# SCH15.net
KiCad netlist of a schematic drawn in Altium Designer
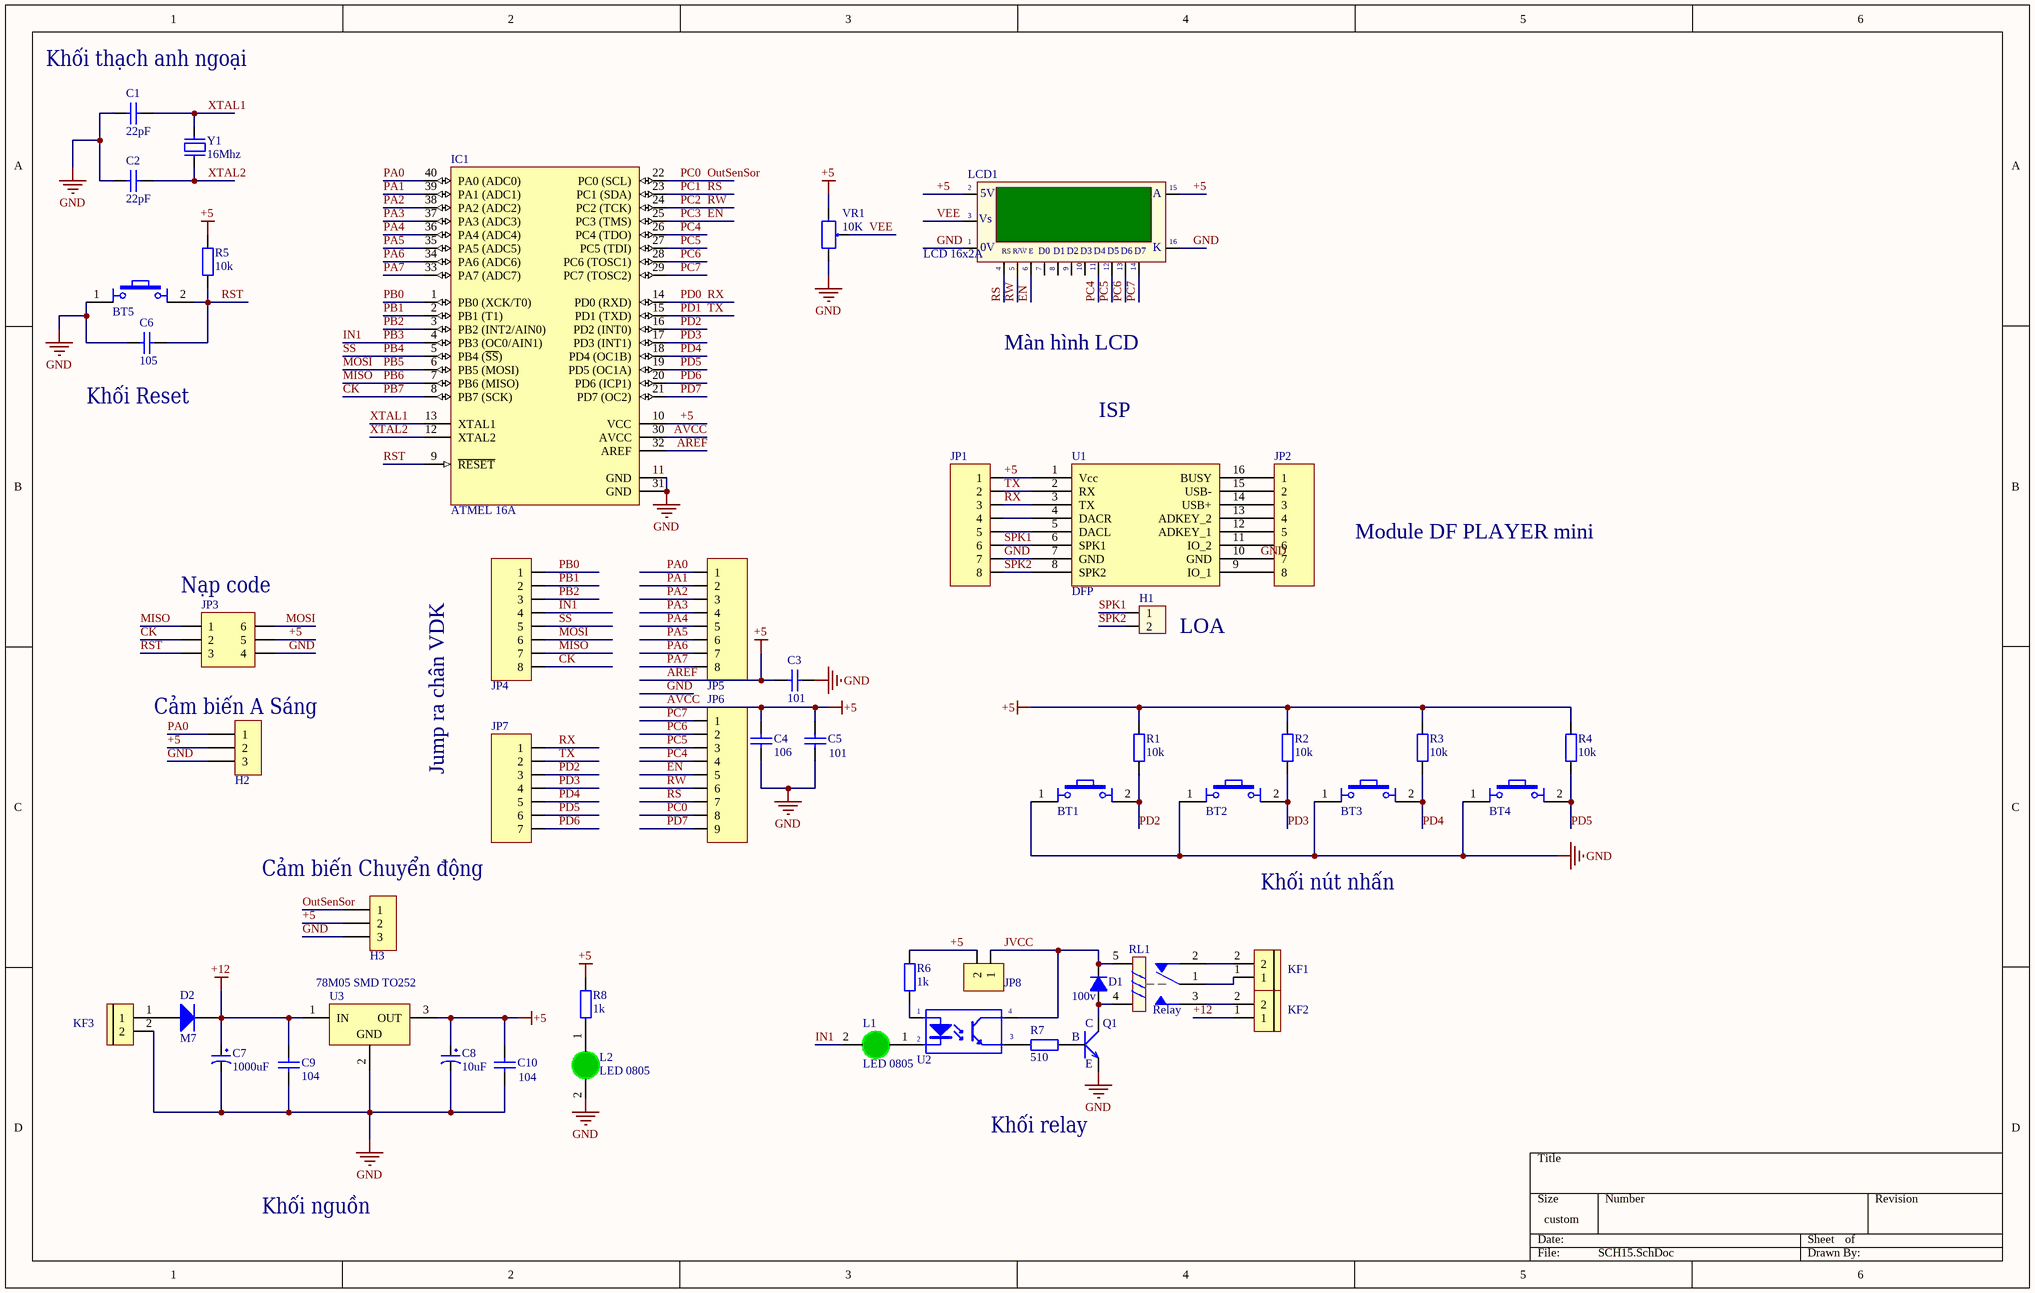
[diagram p0: SCH15.SchDoc]

(export (version "E")
  (design (tool "Eeschema 10.0.6"))
  (components
    (comp (ref "BT1")
      (value "Nut Nhan 4 Chan Cam 6x6")
      (footprint "Nut Nhan 4 Chan Cam 6x6")
      (description "Nut Nhan 4 Chan 6x6mm")
      (libsource (lib "Component") (part "Nut Nhan 4 Chan Cam 6x6"))
    )
    (comp (ref "BT2")
      (value "Nut Nhan 4 Chan Cam 6x6")
      (footprint "Nut Nhan 4 Chan Cam 6x6")
      (description "Nut Nhan 4 Chan 6x6mm")
      (libsource (lib "Component") (part "Nut Nhan 4 Chan Cam 6x6"))
    )
    (comp (ref "BT3")
      (value "Nut Nhan 4 Chan Cam 6x6")
      (footprint "Nut Nhan 4 Chan Cam 6x6")
      (description "Nut Nhan 4 Chan 6x6mm")
      (libsource (lib "Component") (part "Nut Nhan 4 Chan Cam 6x6"))
    )
    (comp (ref "BT4")
      (value "Nut Nhan 4 Chan Cam 6x6")
      (footprint "Nut Nhan 4 Chan Cam 6x6")
      (description "Nut Nhan 4 Chan 6x6mm")
      (libsource (lib "Component") (part "Nut Nhan 4 Chan Cam 6x6"))
    )
    (comp (ref "BT5")
      (value "Nut Nhan 4 Chan Cam 6x6")
      (footprint "Nut Nhan 4 Chan Cam 6x6")
      (description "Nut Nhan 4 Chan 6x6mm")
      (libsource (lib "Component") (part "Nut Nhan 4 Chan Cam 6x6"))
    )
    (comp (ref "C1")
      (value "22pF")
      (footprint "tu 0805")
      (description "Dán")
      (libsource (lib "Tu dien") (part "Tu 0805 22pF 50V 10%"))
    )
    (comp (ref "C2")
      (value "22pF")
      (footprint "tu 0805")
      (description "Dán")
      (libsource (lib "Tu dien") (part "Tu 0805 22pF 50V 10%"))
    )
    (comp (ref "C3")
      (value "101")
      (footprint "tu 0805")
      (description "Dán")
      (libsource (lib "Tu dien") (part "Tu 0805 101 50V 20%"))
    )
    (comp (ref "C4")
      (value "106")
      (footprint "tu 0805")
      (description "Dán")
      (libsource (lib "Tu dien") (part "Tu 0805 106 16V 10%"))
    )
    (comp (ref "C5")
      (value "101")
      (footprint "tu 0805")
      (description "Dán")
      (libsource (lib "Tu dien") (part "Tu 0805 101 50V 20%"))
    )
    (comp (ref "C6")
      (value "105")
      (footprint "tu 0805")
      (description "Dán")
      (libsource (lib "Tu dien") (part "Tu 0805 105 50V 10%"))
    )
    (comp (ref "C7")
      (value "1000uF")
      (footprint "tu hoa 8mm")
      (description "Cắm")
      (libsource (lib "Tu dien") (part "Tu Hoa 1000uF 16V 8x20"))
    )
    (comp (ref "C8")
      (value "10uF")
      (footprint "tu hoa 4mm")
      (description "Cắm")
      (libsource (lib "Tu dien") (part "Tu Hoa 10uF 16V 4x7"))
    )
    (comp (ref "C9")
      (value "104")
      (footprint "tu 0805")
      (description "Dán")
      (libsource (lib "Tu dien") (part "Tu 0805 104 50V 10%"))
    )
    (comp (ref "C10")
      (value "104")
      (footprint "tu 0805")
      (description "Dán")
      (libsource (lib "Tu dien") (part "Tu 0805 104 50V 10%"))
    )
    (comp (ref "D1")
      (value "100v")
      (footprint "DIODE ZENNER SMD SOD80")
      (description "Cắm")
      (libsource (lib "Diode") (part "Diode 1N4148"))
    )
    (comp (ref "D2")
      (value "M7")
      (footprint "DIODE SMA")
      (description "Dán")
      (libsource (lib "Diode") (part "Diode M7 ( 4007 )"))
    )
    (comp (ref "H1")
      (value "Header 2P 2.54 Duc Thang")
      (footprint "XH2.54M-2")
      (description "Cắm")
      (libsource (lib "Header") (part "Header 2P 2.54 Duc Thang"))
    )
    (comp (ref "H2")
      (value "Header 3P 2.54 Duc Thang")
      (footprint "XH2.54M-3")
      (description "Cắm")
      (libsource (lib "Header") (part "Header 3P 2.54 Duc Thang"))
    )
    (comp (ref "H3")
      (value "Header 3P 2.54 Duc Thang")
      (footprint "XH2.54M-3")
      (description "Cắm")
      (libsource (lib "Header") (part "Header 3P 2.54 Duc Thang"))
    )
    (comp (ref "IC1")
      (value "ATMEL 16A")
      (footprint "DIP40/W0.6")
      (description "8-Bit AVR Microcontroller with 16K Bytes of In-System Programmable Flash Memory")
      (libsource (lib "Thu Vien Chuan") (part "ATmega16A-PU"))
    )
    (comp (ref "JP1")
      (value "JP 1x8 2.54")
      (footprint "JP 1x8 DT")
      (description "Cắm")
      (libsource (lib "Jump") (part "JP 1x8 2.54 Duc Thang"))
    )
    (comp (ref "JP2")
      (value "JP 1x8 2.54")
      (footprint "JP 1x8 DT")
      (description "Cắm")
      (libsource (lib "") (part "JP 1x8 2.54 Duc Thang_1"))
    )
    (comp (ref "JP3")
      (value "JP 2x3 2.54")
      (footprint "JP 2x3 DT")
      (description "Cắm")
      (libsource (lib "Jump") (part "JP 2x3 2.54 Duc Thang"))
    )
    (comp (ref "JP4")
      (value "JP 1x8 2.54")
      (footprint "JP 1x8 DT")
      (description "Cắm")
      (libsource (lib "Jump") (part "JP 1x8 2.54 Duc Thang"))
    )
    (comp (ref "JP5")
      (value "JP 1x8 2.54")
      (footprint "JP 1x8 DT")
      (description "Cắm")
      (libsource (lib "") (part "JP 1x8 2.54 Duc Thang_1"))
    )
    (comp (ref "JP6")
      (value "JP 1x9 2.54")
      (footprint "JP 1x9 DT")
      (description "Cắm")
      (libsource (lib "Jump") (part "JP 1x9 2.54 Duc Thang"))
    )
    (comp (ref "JP7")
      (value "JP 1x7 2.54")
      (footprint "JP 1x7 DT")
      (description "Cắm")
      (libsource (lib "Jump") (part "JP 1x7 2.54 Duc Thang"))
    )
    (comp (ref "JP8")
      (value "JP 1x2 2.54")
      (footprint "JP 1x2 DT")
      (description "Cắm")
      (libsource (lib "Jump") (part "JP 1x2 2.54 Duc Thang"))
    )
    (comp (ref "KF1")
      (value "CON 2 KF301")
      (footprint "Con 2 KF301 5.08")
      (description "Cắm")
      (libsource (lib "") (part "CON 2 KF301_1"))
    )
    (comp (ref "KF2")
      (value "CON 2 KF301")
      (footprint "Con 2 KF301 5.08")
      (description "Cắm")
      (libsource (lib "") (part "CON 2 KF301_1"))
    )
    (comp (ref "KF3")
      (value "CON 2 KF301")
      (footprint "Con 2 KF301 5.08")
      (description "Cắm")
      (libsource (lib "Connector") (part "CON 2 KF301"))
    )
    (comp (ref "L1")
      (value "LED 0805")
      (footprint "LED-0805-Green")
      (description "Dán")
      (libsource (lib "Led") (part "LED 0805 Xanh La"))
    )
    (comp (ref "L2")
      (value "LED 0805")
      (footprint "LED-0805-Green")
      (description "Dán")
      (libsource (lib "Led") (part "LED 0805 Xanh La"))
    )
    (comp (ref "LCD1")
      (value "LCD 16x2A")
      (footprint "LCD16X2N")
      (description "LCD dipslay 16 char, 2 line")
      (libsource (lib "Thu Vien Chuan") (part "LCD16x2A"))
    )
    (comp (ref "Q1")
      (value "SMD-TRANSISTORS-NPN-25V-500MW(SOT-23)")
      (footprint "SOT 23-3")
      (description "Bipolar (BJT) Transistor NPN 25 V 500 mA 150MHz 300 mW Surface Mount SOT-23")
      (fields (field (name "MF") "UMW") (field (name "MP") "S8050"))
      (libsource (lib "05.IC") (part "SMD-TRANSISTORS-NPN-25V-500MW(SOT-23)"))
    )
    (comp (ref "R1")
      (value "10k")
      (footprint "tro smd 0805")
      (description "Dán")
      (libsource (lib "Dien Tro") (part "Tro 0805 1% 10k"))
    )
    (comp (ref "R2")
      (value "10k")
      (footprint "tro smd 0805")
      (description "Dán")
      (libsource (lib "Dien Tro") (part "Tro 0805 1% 10k"))
    )
    (comp (ref "R3")
      (value "10k")
      (footprint "tro smd 0805")
      (description "Dán")
      (libsource (lib "Dien Tro") (part "Tro 0805 1% 10k"))
    )
    (comp (ref "R4")
      (value "10k")
      (footprint "tro smd 0805")
      (description "Dán")
      (libsource (lib "Dien Tro") (part "Tro 0805 1% 10k"))
    )
    (comp (ref "R5")
      (value "10k")
      (footprint "tro smd 0805")
      (description "Dán")
      (libsource (lib "Dien Tro") (part "Tro 0805 1% 10k"))
    )
    (comp (ref "R6")
      (value "1k")
      (footprint "tro smd 0805")
      (description "Dán")
      (libsource (lib "Dien Tro") (part "Tro 0805 1% 1k"))
    )
    (comp (ref "R7")
      (value "510")
      (footprint "tro smd 0805")
      (description "Dán")
      (libsource (lib "Dien Tro") (part "Tro 0805 1% 1k"))
    )
    (comp (ref "R8")
      (value "1k")
      (footprint "tro smd 0805")
      (description "Dán")
      (libsource (lib "Dien Tro") (part "Tro 0805 1% 1k"))
    )
    (comp (ref "RL1")
      (value "Relay")
      (footprint "Relay 5 Chan SRD")
      (description "Relay 5 Chan")
      (libsource (lib "Component") (part "Relay 5 Chan SRD"))
    )
    (comp (ref "U1")
      (value "DFP")
      (footprint "DFPlayer")
      (description "DFPlayer")
      (libsource (lib "Module1") (part "DFPlayer"))
    )
    (comp (ref "U2")
      (value "OPTO PC817 DIP4")
      (footprint "DIP4")
      (description "Single Opto")
      (libsource (lib "IC") (part "OPTO PC817 DIP4"))
    )
    (comp (ref "U3")
      (value "78M05 SMD TO252")
      (footprint "TO252")
      (description "Dán")
      (libsource (lib "IC") (part "78M05 SMD TO252"))
    )
    (comp (ref "VR1")
      (value "10K")
      (footprint "Bien Tro Vi Chinh Dung")
      (description "Cắm")
      (libsource (lib "Dien Tro") (part "Bien Tro Tinh Chinh 1K Dung"))
    )
    (comp (ref "Y1")
      (value "16Mhz")
      (footprint "Thach Anh 2 chan cam")
      (description "Crystal For all Crystal 2pin.")
      (libsource (lib "Component") (part "Thach Anh 2 chan Cam"))
    )
  )
  (nets
    (net (code "1") (name "+5") (class "Default")
      (node (ref "C10") (pin "1") (pinfunction "1_1") (pintype "passive"))
      (node (ref "C3") (pin "1") (pinfunction "1_1") (pintype "passive"))
      (node (ref "C4") (pin "2") (pinfunction "2_2") (pintype "passive"))
      (node (ref "C5") (pin "1") (pinfunction "1_1") (pintype "passive"))
      (node (ref "C8") (pin "1") (pinfunction "1_1") (pintype "passive"))
      (node (ref "H2") (pin "2") (pinfunction "2_2") (pintype "passive"))
      (node (ref "H3") (pin "2") (pinfunction "2_2") (pintype "passive"))
      (node (ref "IC1") (pin "10") (pinfunction "VCC_10") (pintype "power_in"))
      (node (ref "IC1") (pin "30") (pinfunction "AVCC_30") (pintype "power_in"))
      (node (ref "IC1") (pin "32") (pinfunction "AREF_32") (pintype "power_in"))
      (node (ref "JP1") (pin "1") (pinfunction "1_1") (pintype "passive"))
      (node (ref "JP3") (pin "5") (pinfunction "5_5") (pintype "passive"))
      (node (ref "JP8") (pin "2") (pinfunction "2_2") (pintype "passive"))
      (node (ref "LCD1") (pin "15") (pinfunction "A_15") (pintype "passive"))
      (node (ref "LCD1") (pin "2") (pinfunction "VDD_2") (pintype "passive"))
      (node (ref "R1") (pin "2") (pinfunction "2_2") (pintype "passive"))
      (node (ref "R2") (pin "2") (pinfunction "2_2") (pintype "passive"))
      (node (ref "R3") (pin "2") (pinfunction "2_2") (pintype "passive"))
      (node (ref "R4") (pin "2") (pinfunction "2_2") (pintype "passive"))
      (node (ref "R5") (pin "2") (pinfunction "2_2") (pintype "passive"))
      (node (ref "R6") (pin "1") (pinfunction "1_1") (pintype "passive"))
      (node (ref "R8") (pin "2") (pinfunction "2_2") (pintype "passive"))
      (node (ref "U1") (pin "1") (pinfunction "Vcc_1") (pintype "passive"))
      (node (ref "U3") (pin "3") (pinfunction "OUT_3") (pintype "power_in"))
      (node (ref "VR1") (pin "1") (pinfunction "1_1") (pintype "passive"))
    )
    (net (code "2") (name "+12") (class "Default")
      (node (ref "C7") (pin "1") (pinfunction "1_1") (pintype "passive"))
      (node (ref "C9") (pin "1") (pinfunction "1_1") (pintype "passive"))
      (node (ref "D2") (pin "2") (pinfunction "K_2") (pintype "passive"))
      (node (ref "KF2") (pin "1") (pinfunction "1_1") (pintype "passive"))
      (node (ref "U3") (pin "1") (pinfunction "IN_1") (pintype "power_in"))
    )
    (net (code "3") (name "/CK") (class "Default")
      (node (ref "IC1") (pin "8") (pinfunction "PB7_(SCK)_8") (pintype "bidirectional"))
      (node (ref "JP3") (pin "2") (pinfunction "2_2") (pintype "passive"))
      (node (ref "JP4") (pin "8") (pinfunction "8_8") (pintype "passive"))
    )
    (net (code "4") (name "/EN") (class "Default")
      (node (ref "IC1") (pin "25") (pinfunction "PC3_(TMS)_25") (pintype "bidirectional"))
      (node (ref "JP6") (pin "5") (pinfunction "5_5") (pintype "passive"))
      (node (ref "LCD1") (pin "6") (pinfunction "~{EN}_6") (pintype "passive"))
    )
    (net (code "5") (name "/IN1") (class "Default")
      (node (ref "IC1") (pin "4") (pinfunction "PB3_(OC0/AIN1)_4") (pintype "bidirectional"))
      (node (ref "JP4") (pin "4") (pinfunction "4_4") (pintype "passive"))
      (node (ref "L1") (pin "2") (pinfunction "K_2") (pintype "passive"))
    )
    (net (code "6") (name "/JVCC") (class "Default")
      (node (ref "D1") (pin "2") (pinfunction "K_2") (pintype "passive"))
      (node (ref "JP8") (pin "1") (pinfunction "1_1") (pintype "passive"))
      (node (ref "RL1") (pin "5") (pinfunction "5_5") (pintype "passive"))
      (node (ref "U2") (pin "4") (pinfunction "C_4") (pintype "passive"))
    )
    (net (code "7") (name "/MISO") (class "Default")
      (node (ref "IC1") (pin "7") (pinfunction "PB6_(MISO)_7") (pintype "bidirectional"))
      (node (ref "JP3") (pin "1") (pinfunction "1_1") (pintype "passive"))
      (node (ref "JP4") (pin "7") (pinfunction "7_7") (pintype "passive"))
    )
    (net (code "8") (name "/MOSI") (class "Default")
      (node (ref "IC1") (pin "6") (pinfunction "PB5_(MOSI)_6") (pintype "bidirectional"))
      (node (ref "JP3") (pin "6") (pinfunction "6_6") (pintype "passive"))
      (node (ref "JP4") (pin "6") (pinfunction "6_6") (pintype "passive"))
    )
    (net (code "9") (name "/OutSenSor") (class "Default")
      (node (ref "H3") (pin "1") (pinfunction "1_1") (pintype "passive"))
      (node (ref "IC1") (pin "22") (pinfunction "PC0_(SCL)_22") (pintype "bidirectional"))
      (node (ref "JP6") (pin "8") (pinfunction "8_8") (pintype "passive"))
    )
    (net (code "10") (name "/PA0") (class "Default")
      (node (ref "H2") (pin "1") (pinfunction "1_1") (pintype "passive"))
      (node (ref "IC1") (pin "40") (pinfunction "PA0_(ADC0)_40") (pintype "bidirectional"))
      (node (ref "JP5") (pin "1") (pinfunction "1_1") (pintype "passive"))
    )
    (net (code "11") (name "/PA1") (class "Default")
      (node (ref "IC1") (pin "39") (pinfunction "PA1_(ADC1)_39") (pintype "bidirectional"))
      (node (ref "JP5") (pin "2") (pinfunction "2_2") (pintype "passive"))
    )
    (net (code "12") (name "/PA2") (class "Default")
      (node (ref "IC1") (pin "38") (pinfunction "PA2_(ADC2)_38") (pintype "bidirectional"))
      (node (ref "JP5") (pin "3") (pinfunction "3_3") (pintype "passive"))
    )
    (net (code "13") (name "/PA3") (class "Default")
      (node (ref "IC1") (pin "37") (pinfunction "PA3_(ADC3)_37") (pintype "bidirectional"))
      (node (ref "JP5") (pin "4") (pinfunction "4_4") (pintype "passive"))
    )
    (net (code "14") (name "/PA4") (class "Default")
      (node (ref "IC1") (pin "36") (pinfunction "PA4_(ADC4)_36") (pintype "bidirectional"))
      (node (ref "JP5") (pin "5") (pinfunction "5_5") (pintype "passive"))
    )
    (net (code "15") (name "/PA5") (class "Default")
      (node (ref "IC1") (pin "35") (pinfunction "PA5_(ADC5)_35") (pintype "bidirectional"))
      (node (ref "JP5") (pin "6") (pinfunction "6_6") (pintype "passive"))
    )
    (net (code "16") (name "/PA6") (class "Default")
      (node (ref "IC1") (pin "34") (pinfunction "PA6_(ADC6)_34") (pintype "bidirectional"))
      (node (ref "JP5") (pin "7") (pinfunction "7_7") (pintype "passive"))
    )
    (net (code "17") (name "/PA7") (class "Default")
      (node (ref "IC1") (pin "33") (pinfunction "PA7_(ADC7)_33") (pintype "bidirectional"))
      (node (ref "JP5") (pin "8") (pinfunction "8_8") (pintype "passive"))
    )
    (net (code "18") (name "/PB0") (class "Default")
      (node (ref "IC1") (pin "1") (pinfunction "PB0_(XCK/T0)_1") (pintype "bidirectional"))
      (node (ref "JP4") (pin "1") (pinfunction "1_1") (pintype "passive"))
    )
    (net (code "19") (name "/PB1") (class "Default")
      (node (ref "IC1") (pin "2") (pinfunction "PB1_(T1)_2") (pintype "bidirectional"))
      (node (ref "JP4") (pin "2") (pinfunction "2_2") (pintype "passive"))
    )
    (net (code "20") (name "/PB2") (class "Default")
      (node (ref "IC1") (pin "3") (pinfunction "PB2_(INT2/AIN0)_3") (pintype "bidirectional"))
      (node (ref "JP4") (pin "3") (pinfunction "3_3") (pintype "passive"))
    )
    (net (code "21") (name "/PB4") (class "Default")
      (node (ref "IC1") (pin "5") (pinfunction "PB4_(~{SS})_5") (pintype "bidirectional"))
      (node (ref "JP4") (pin "5") (pinfunction "5_5") (pintype "passive"))
    )
    (net (code "22") (name "/PC1") (class "Default")
      (node (ref "IC1") (pin "23") (pinfunction "PC1_(SDA)_23") (pintype "bidirectional"))
      (node (ref "JP6") (pin "7") (pinfunction "7_7") (pintype "passive"))
      (node (ref "LCD1") (pin "4") (pinfunction "RS_4") (pintype "passive"))
    )
    (net (code "23") (name "/PC2") (class "Default")
      (node (ref "IC1") (pin "24") (pinfunction "PC2_(TCK)_24") (pintype "bidirectional"))
      (node (ref "JP6") (pin "6") (pinfunction "6_6") (pintype "passive"))
      (node (ref "LCD1") (pin "5") (pinfunction "R/~{W}_5") (pintype "passive"))
    )
    (net (code "24") (name "/PC4") (class "Default")
      (node (ref "IC1") (pin "26") (pinfunction "PC4_(TDO)_26") (pintype "bidirectional"))
      (node (ref "JP6") (pin "4") (pinfunction "4_4") (pintype "passive"))
      (node (ref "LCD1") (pin "11") (pinfunction "D4_11") (pintype "passive"))
    )
    (net (code "25") (name "/PC5") (class "Default")
      (node (ref "IC1") (pin "27") (pinfunction "PC5_(TDI)_27") (pintype "bidirectional"))
      (node (ref "JP6") (pin "3") (pinfunction "3_3") (pintype "passive"))
      (node (ref "LCD1") (pin "12") (pinfunction "D5_12") (pintype "passive"))
    )
    (net (code "26") (name "/PC6") (class "Default")
      (node (ref "IC1") (pin "28") (pinfunction "PC6_(TOSC1)_28") (pintype "bidirectional"))
      (node (ref "JP6") (pin "2") (pinfunction "2_2") (pintype "passive"))
      (node (ref "LCD1") (pin "13") (pinfunction "D6_13") (pintype "passive"))
    )
    (net (code "27") (name "/PC7") (class "Default")
      (node (ref "IC1") (pin "29") (pinfunction "PC7_(TOSC2)_29") (pintype "bidirectional"))
      (node (ref "JP6") (pin "1") (pinfunction "1_1") (pintype "passive"))
      (node (ref "LCD1") (pin "14") (pinfunction "D7_14") (pintype "passive"))
    )
    (net (code "28") (name "/PD0") (class "Default")
      (node (ref "IC1") (pin "14") (pinfunction "PD0_(RXD)_14") (pintype "bidirectional"))
      (node (ref "JP1") (pin "3") (pinfunction "3_3") (pintype "passive"))
      (node (ref "JP7") (pin "1") (pinfunction "1_1") (pintype "passive"))
      (node (ref "U1") (pin "3") (pinfunction "TX_3") (pintype "passive"))
    )
    (net (code "29") (name "/PD1") (class "Default")
      (node (ref "IC1") (pin "15") (pinfunction "PD1_(TXD)_15") (pintype "bidirectional"))
      (node (ref "JP1") (pin "2") (pinfunction "2_2") (pintype "passive"))
      (node (ref "JP7") (pin "2") (pinfunction "2_2") (pintype "passive"))
      (node (ref "U1") (pin "2") (pinfunction "RX_2") (pintype "passive"))
    )
    (net (code "30") (name "/PD2") (class "Default")
      (node (ref "BT1") (pin "2") (pintype "passive"))
      (node (ref "IC1") (pin "16") (pinfunction "PD2_(INT0)_16") (pintype "bidirectional"))
      (node (ref "JP7") (pin "3") (pinfunction "3_3") (pintype "passive"))
      (node (ref "R1") (pin "1") (pinfunction "1_1") (pintype "passive"))
    )
    (net (code "31") (name "/PD3") (class "Default")
      (node (ref "BT2") (pin "2") (pintype "passive"))
      (node (ref "IC1") (pin "17") (pinfunction "PD3_(INT1)_17") (pintype "bidirectional"))
      (node (ref "JP7") (pin "4") (pinfunction "4_4") (pintype "passive"))
      (node (ref "R2") (pin "1") (pinfunction "1_1") (pintype "passive"))
    )
    (net (code "32") (name "/PD4") (class "Default")
      (node (ref "BT3") (pin "2") (pintype "passive"))
      (node (ref "IC1") (pin "18") (pinfunction "PD4_(OC1B)_18") (pintype "bidirectional"))
      (node (ref "JP7") (pin "5") (pinfunction "5_5") (pintype "passive"))
      (node (ref "R3") (pin "1") (pinfunction "1_1") (pintype "passive"))
    )
    (net (code "33") (name "/PD5") (class "Default")
      (node (ref "BT4") (pin "2") (pintype "passive"))
      (node (ref "IC1") (pin "19") (pinfunction "PD5_(OC1A)_19") (pintype "bidirectional"))
      (node (ref "JP7") (pin "6") (pinfunction "6_6") (pintype "passive"))
      (node (ref "R4") (pin "1") (pinfunction "1_1") (pintype "passive"))
    )
    (net (code "34") (name "/PD6") (class "Default")
      (node (ref "IC1") (pin "20") (pinfunction "PD6_(ICP1)_20") (pintype "bidirectional"))
      (node (ref "JP7") (pin "7") (pinfunction "7_7") (pintype "passive"))
    )
    (net (code "35") (name "/PD7") (class "Default")
      (node (ref "IC1") (pin "21") (pinfunction "PD7_(OC2)_21") (pintype "bidirectional"))
      (node (ref "JP6") (pin "9") (pinfunction "9_9") (pintype "passive"))
    )
    (net (code "36") (name "/RST") (class "Default")
      (node (ref "BT5") (pin "2") (pintype "passive"))
      (node (ref "C6") (pin "2") (pinfunction "2_2") (pintype "passive"))
      (node (ref "IC1") (pin "9") (pinfunction "~{RESET}_9") (pintype "input"))
      (node (ref "JP3") (pin "3") (pinfunction "3_3") (pintype "passive"))
      (node (ref "R5") (pin "1") (pinfunction "1_1") (pintype "passive"))
    )
    (net (code "37") (name "/SPK1") (class "Default")
      (node (ref "H1") (pin "1") (pinfunction "1_1") (pintype "passive"))
      (node (ref "JP1") (pin "6") (pinfunction "6_6") (pintype "passive"))
      (node (ref "U1") (pin "6") (pinfunction "SPK1_6") (pintype "passive"))
    )
    (net (code "38") (name "/SPK2") (class "Default")
      (node (ref "H1") (pin "2") (pinfunction "2_2") (pintype "passive"))
      (node (ref "JP1") (pin "8") (pinfunction "8_8") (pintype "passive"))
      (node (ref "U1") (pin "8") (pinfunction "SPK2_8") (pintype "passive"))
    )
    (net (code "39") (name "/VEE") (class "Default")
      (node (ref "LCD1") (pin "3") (pinfunction "VEE_3") (pintype "passive"))
      (node (ref "VR1") (pin "2") (pinfunction "2_2") (pintype "passive"))
    )
    (net (code "40") (name "/XTAL1") (class "Default")
      (node (ref "C1") (pin "1") (pinfunction "1_1") (pintype "passive"))
      (node (ref "IC1") (pin "13") (pinfunction "XTAL1_13") (pintype "passive"))
      (node (ref "Y1") (pin "2") (pinfunction "2_2") (pintype "passive"))
    )
    (net (code "41") (name "/XTAL2") (class "Default")
      (node (ref "C2") (pin "1") (pinfunction "1_1") (pintype "passive"))
      (node (ref "IC1") (pin "12") (pinfunction "XTAL2_12") (pintype "passive"))
      (node (ref "Y1") (pin "1") (pinfunction "1_1") (pintype "passive"))
    )
    (net (code "42") (name "GND") (class "Default")
      (node (ref "BT1") (pin "1") (pintype "passive"))
      (node (ref "BT2") (pin "1") (pintype "passive"))
      (node (ref "BT3") (pin "1") (pintype "passive"))
      (node (ref "BT4") (pin "1") (pintype "passive"))
      (node (ref "BT5") (pin "1") (pintype "passive"))
      (node (ref "C1") (pin "2") (pinfunction "2_2") (pintype "passive"))
      (node (ref "C10") (pin "2") (pinfunction "2_2") (pintype "passive"))
      (node (ref "C2") (pin "2") (pinfunction "2_2") (pintype "passive"))
      (node (ref "C3") (pin "2") (pinfunction "2_2") (pintype "passive"))
      (node (ref "C4") (pin "1") (pinfunction "1_1") (pintype "passive"))
      (node (ref "C5") (pin "2") (pinfunction "2_2") (pintype "passive"))
      (node (ref "C6") (pin "1") (pinfunction "1_1") (pintype "passive"))
      (node (ref "C7") (pin "2") (pinfunction "2_2") (pintype "passive"))
      (node (ref "C8") (pin "2") (pinfunction "2_2") (pintype "passive"))
      (node (ref "C9") (pin "2") (pinfunction "2_2") (pintype "passive"))
      (node (ref "H2") (pin "3") (pinfunction "3_3") (pintype "passive"))
      (node (ref "H3") (pin "3") (pinfunction "3_3") (pintype "passive"))
      (node (ref "IC1") (pin "11") (pinfunction "GND_11") (pintype "power_in"))
      (node (ref "IC1") (pin "31") (pinfunction "GND_31") (pintype "power_in"))
      (node (ref "JP1") (pin "7") (pinfunction "7_7") (pintype "passive"))
      (node (ref "JP2") (pin "7") (pinfunction "7_7") (pintype "passive"))
      (node (ref "JP3") (pin "4") (pinfunction "4_4") (pintype "passive"))
      (node (ref "KF3") (pin "2") (pinfunction "2_2") (pintype "passive"))
      (node (ref "L2") (pin "2") (pinfunction "K_2") (pintype "passive"))
      (node (ref "LCD1") (pin "1") (pinfunction "GND_1") (pintype "passive"))
      (node (ref "LCD1") (pin "16") (pinfunction "K_16") (pintype "passive"))
      (node (ref "Q1") (pin "2") (pinfunction "E_2") (pintype "passive"))
      (node (ref "U1") (pin "10") (pinfunction "GND_10") (pintype "passive"))
      (node (ref "U1") (pin "7") (pinfunction "GND_7") (pintype "passive"))
      (node (ref "U3") (pin "2") (pinfunction "GND_2") (pintype "power_in"))
      (node (ref "VR1") (pin "3") (pinfunction "3_3") (pintype "passive"))
    )
    (net (code "43") (name "Net-(D1-A)") (class "Default")
      (node (ref "D1") (pin "1") (pinfunction "A_1") (pintype "passive"))
      (node (ref "Q1") (pin "3") (pinfunction "C_3") (pintype "passive"))
      (node (ref "RL1") (pin "4") (pinfunction "4_4") (pintype "passive"))
    )
    (net (code "44") (name "Net-(D2-A)") (class "Default")
      (node (ref "D2") (pin "1") (pinfunction "A_1") (pintype "passive"))
      (node (ref "KF3") (pin "1") (pinfunction "1_1") (pintype "passive"))
    )
    (net (code "45") (name "Net-(KF1-Pad1)") (class "Default")
      (node (ref "KF1") (pin "1") (pinfunction "1_1") (pintype "passive"))
      (node (ref "RL1") (pin "1") (pinfunction "1_1") (pintype "passive"))
    )
    (net (code "46") (name "Net-(KF1-Pad2)") (class "Default")
      (node (ref "KF1") (pin "2") (pinfunction "2_2") (pintype "passive"))
      (node (ref "RL1") (pin "2") (pinfunction "2_2") (pintype "passive"))
    )
    (net (code "47") (name "Net-(KF2-Pad2)") (class "Default")
      (node (ref "KF2") (pin "2") (pinfunction "2_2") (pintype "passive"))
      (node (ref "RL1") (pin "3") (pinfunction "3_3") (pintype "passive"))
    )
    (net (code "48") (name "Net-(L1-A)") (class "Default")
      (node (ref "L1") (pin "1") (pinfunction "A_1") (pintype "passive"))
      (node (ref "U2") (pin "2") (pinfunction "K_2") (pintype "passive"))
    )
    (net (code "49") (name "Net-(L2-A)") (class "Default")
      (node (ref "L2") (pin "1") (pinfunction "A_1") (pintype "passive"))
      (node (ref "R8") (pin "1") (pinfunction "1_1") (pintype "passive"))
    )
    (net (code "50") (name "Net-(Q1-B)") (class "Default")
      (node (ref "Q1") (pin "1") (pinfunction "B_1") (pintype "passive"))
      (node (ref "R7") (pin "1") (pinfunction "1_1") (pintype "passive"))
    )
    (net (code "51") (name "Net-(U1-ADKEY_1)") (class "Default")
      (node (ref "JP2") (pin "5") (pinfunction "5_5") (pintype "passive"))
      (node (ref "U1") (pin "12") (pinfunction "ADKEY_1_12") (pintype "passive"))
    )
    (net (code "52") (name "Net-(U1-ADKEY_2)") (class "Default")
      (node (ref "JP2") (pin "4") (pinfunction "4_4") (pintype "passive"))
      (node (ref "U1") (pin "13") (pinfunction "ADKEY_2_13") (pintype "passive"))
    )
    (net (code "53") (name "Net-(U1-BUSY)") (class "Default")
      (node (ref "JP2") (pin "1") (pinfunction "1_1") (pintype "passive"))
      (node (ref "U1") (pin "16") (pinfunction "BUSY_16") (pintype "passive"))
    )
    (net (code "54") (name "Net-(U1-DACL)") (class "Default")
      (node (ref "JP1") (pin "5") (pinfunction "5_5") (pintype "passive"))
      (node (ref "U1") (pin "5") (pinfunction "DACL_5") (pintype "passive"))
    )
    (net (code "55") (name "Net-(U1-DACR)") (class "Default")
      (node (ref "JP1") (pin "4") (pinfunction "4_4") (pintype "passive"))
      (node (ref "U1") (pin "4") (pinfunction "DACR_4") (pintype "passive"))
    )
    (net (code "56") (name "Net-(U1-IO_1)") (class "Default")
      (node (ref "JP2") (pin "8") (pinfunction "8_8") (pintype "passive"))
      (node (ref "U1") (pin "9") (pinfunction "IO_1_9") (pintype "passive"))
    )
    (net (code "57") (name "Net-(U1-IO_2)") (class "Default")
      (node (ref "JP2") (pin "6") (pinfunction "6_6") (pintype "passive"))
      (node (ref "U1") (pin "11") (pinfunction "IO_2_11") (pintype "passive"))
    )
    (net (code "58") (name "Net-(U1-USB+)") (class "Default")
      (node (ref "JP2") (pin "3") (pinfunction "3_3") (pintype "passive"))
      (node (ref "U1") (pin "14") (pinfunction "USB+_14") (pintype "passive"))
    )
    (net (code "59") (name "Net-(U1-USB-)") (class "Default")
      (node (ref "JP2") (pin "2") (pinfunction "2_2") (pintype "passive"))
      (node (ref "U1") (pin "15") (pinfunction "USB-_15") (pintype "passive"))
    )
    (net (code "60") (name "Net-(U2-A)") (class "Default")
      (node (ref "R6") (pin "2") (pinfunction "2_2") (pintype "passive"))
      (node (ref "U2") (pin "1") (pinfunction "A_1") (pintype "passive"))
    )
    (net (code "61") (name "Net-(U2-E)") (class "Default")
      (node (ref "R7") (pin "2") (pinfunction "2_2") (pintype "passive"))
      (node (ref "U2") (pin "3") (pinfunction "E_3") (pintype "passive"))
    )
    (net (code "62") (name "unconnected-(LCD1-D0-Pad7)") (class "Default")
      (node (ref "LCD1") (pin "7") (pinfunction "D0_7") (pintype "passive"))
    )
    (net (code "63") (name "unconnected-(LCD1-D1-Pad8)") (class "Default")
      (node (ref "LCD1") (pin "8") (pinfunction "D1_8") (pintype "passive"))
    )
    (net (code "64") (name "unconnected-(LCD1-D2-Pad9)") (class "Default")
      (node (ref "LCD1") (pin "9") (pinfunction "D2_9") (pintype "passive"))
    )
    (net (code "65") (name "unconnected-(LCD1-D3-Pad10)") (class "Default")
      (node (ref "LCD1") (pin "10") (pinfunction "D3_10") (pintype "passive"))
    )
  )
)
